# QCLogic_Rev_A_Sht5_MEMS.net
KiCad netlist of a schematic drawn in Altium Designer
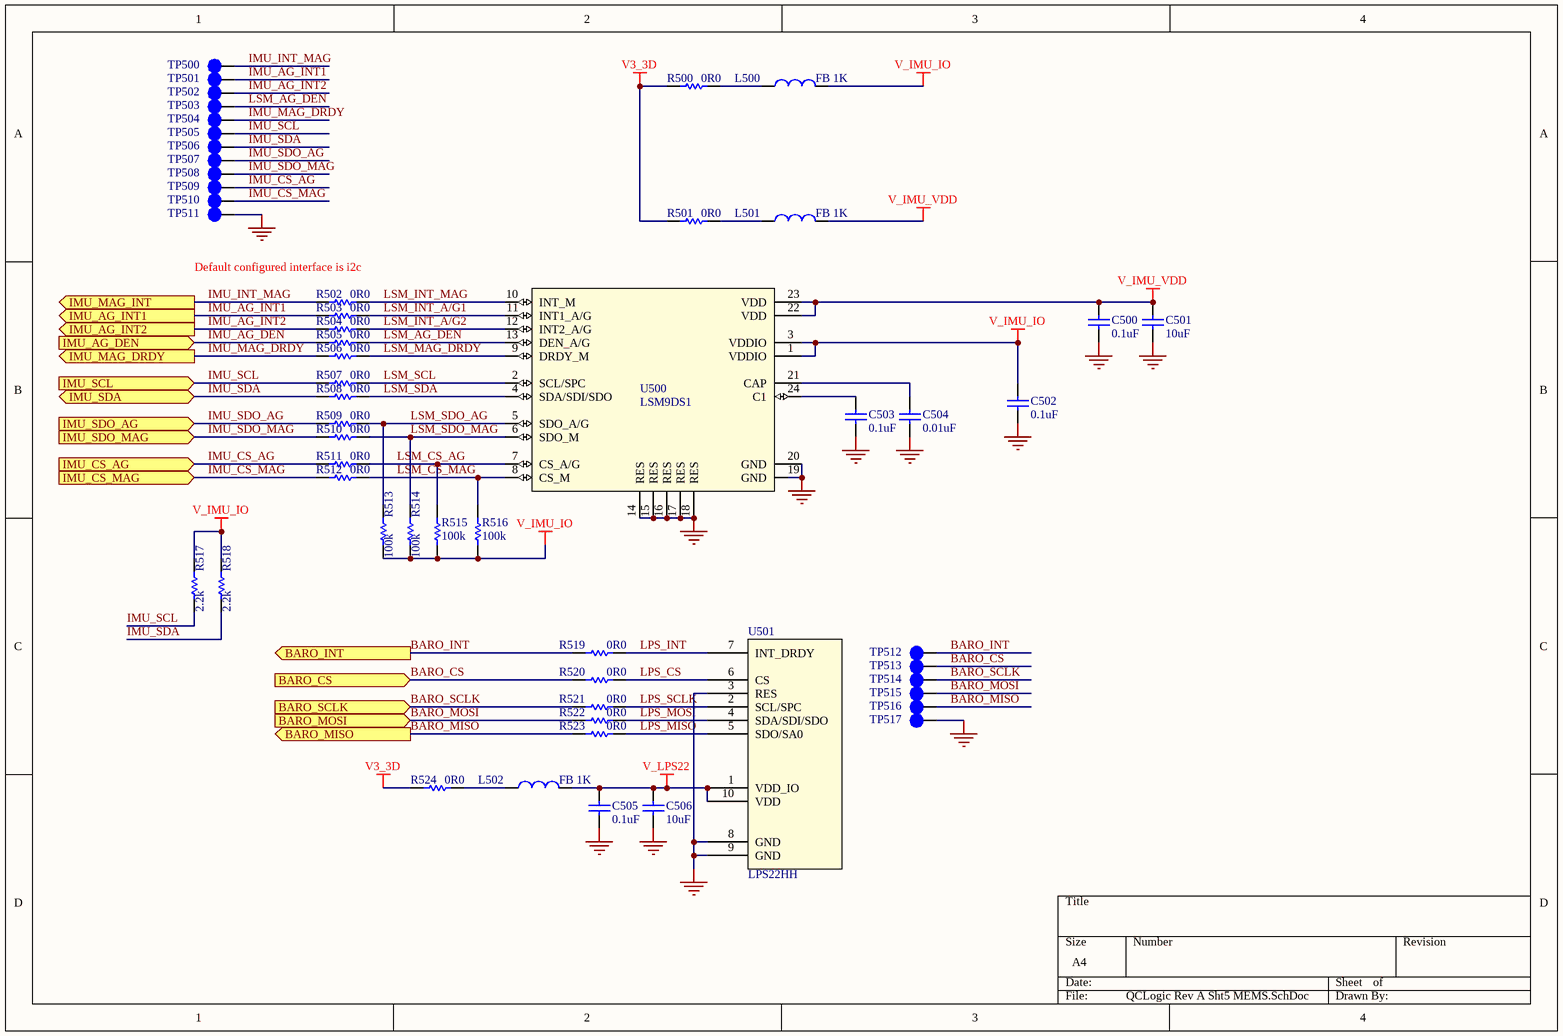
[diagram p0: QCLogic Rev A Sht5 MEMS.SchDoc]

(export (version "E")
  (design (tool "Eeschema 10.0.6"))
  (components
    (comp (ref "C500")
      (value "0.1uF")
      (footprint "SMD CAP 0402")
      (description "CAP CER 0.1UF 25V X7R 0402")
      (fields (field (name "2. MANUFACTURER PART NUMBER") "CC0402KRX7R8BB104"))
      (libsource (lib "SBCLib") (part "CAP MLCC SMD"))
    )
    (comp (ref "C501")
      (value "10uF")
      (footprint "SMD CAP 0805")
      (description "CAP CER 10UF 25V X5R 0805")
      (fields (field (name "2. MANUFACTURER PART NUMBER") "TMK212BBJ106KG-T"))
      (libsource (lib "SBCLib") (part "CAP MLCC SMD"))
    )
    (comp (ref "C502")
      (value "0.1uF")
      (footprint "SMD CAP 0402")
      (description "CAP CER 0.1UF 25V X7R 0402")
      (fields (field (name "2. MANUFACTURER PART NUMBER") "CC0402KRX7R8BB104"))
      (libsource (lib "SBCLib") (part "CAP MLCC SMD"))
    )
    (comp (ref "C503")
      (value "0.1uF")
      (footprint "SMD CAP 0402")
      (description "CAP CER 0.1UF 25V X7R 0402")
      (fields (field (name "2. MANUFACTURER PART NUMBER") "CC0402KRX7R8BB104"))
      (libsource (lib "SBCLib") (part "CAP MLCC SMD"))
    )
    (comp (ref "C504")
      (value "0.01uF")
      (footprint "SMD CAP 0402")
      (description "CAP CER 10000PF 16V X7R 0402")
      (fields (field (name "2. MANUFACTURER PART NUMBER") "0402B103K160CT"))
      (libsource (lib "SBCLib") (part "CAP MLCC SMD"))
    )
    (comp (ref "C505")
      (value "0.1uF")
      (footprint "SMD CAP 0402")
      (description "CAP CER 0.1UF 25V X7R 0402")
      (fields (field (name "2. MANUFACTURER PART NUMBER") "CC0402KRX7R8BB104"))
      (libsource (lib "SBCLib") (part "CAP MLCC SMD"))
    )
    (comp (ref "C506")
      (value "10uF")
      (footprint "SMD CAP 0805")
      (description "CAP CER 10UF 25V X5R 0805")
      (fields (field (name "2. MANUFACTURER PART NUMBER") "TMK212BBJ106KG-T"))
      (libsource (lib "SBCLib") (part "CAP MLCC SMD"))
    )
    (comp (ref "L500")
      (value "FB 1K")
      (footprint "SMD RES 0402")
      (description "FERRITE BEAD 1 KOHM 0402 1LN")
      (fields (field (name "2. MANUFACTURER PART NUMBER") "BLM15HD102SN1D"))
      (libsource (lib "SBCLib") (part "INDUCTOR"))
    )
    (comp (ref "L501")
      (value "FB 1K")
      (footprint "SMD RES 0402")
      (description "FERRITE BEAD 1 KOHM 0402 1LN")
      (fields (field (name "2. MANUFACTURER PART NUMBER") "BLM15HD102SN1D"))
      (libsource (lib "SBCLib") (part "INDUCTOR"))
    )
    (comp (ref "L502")
      (value "FB 1K")
      (footprint "SMD RES 0402")
      (description "FERRITE BEAD 1 KOHM 0402 1LN")
      (fields (field (name "2. MANUFACTURER PART NUMBER") "BLM15HD102SN1D"))
      (libsource (lib "SBCLib") (part "INDUCTOR"))
    )
    (comp (ref "R500")
      (value "0R0")
      (footprint "SMD RES 0402")
      (description "RES SMD 0 OHM JUMPER 1/16W 0402")
      (fields (field (name "2. MANUFACTURER PART NUMBER") "RC0402FR-070RL"))
      (libsource (lib "SBCLib") (part "RES SMD"))
    )
    (comp (ref "R501")
      (value "0R0")
      (footprint "SMD RES 0402")
      (description "RES SMD 0 OHM JUMPER 1/16W 0402")
      (fields (field (name "2. MANUFACTURER PART NUMBER") "RC0402FR-070RL"))
      (libsource (lib "SBCLib") (part "RES SMD"))
    )
    (comp (ref "R502")
      (value "0R0")
      (footprint "SMD RES 0402")
      (description "RES SMD 0 OHM JUMPER 1/16W 0402")
      (fields (field (name "2. MANUFACTURER PART NUMBER") "RC0402FR-070RL"))
      (libsource (lib "SBCLib") (part "RES SMD"))
    )
    (comp (ref "R503")
      (value "0R0")
      (footprint "SMD RES 0402")
      (description "RES SMD 0 OHM JUMPER 1/16W 0402")
      (fields (field (name "2. MANUFACTURER PART NUMBER") "RC0402FR-070RL"))
      (libsource (lib "SBCLib") (part "RES SMD"))
    )
    (comp (ref "R504")
      (value "0R0")
      (footprint "SMD RES 0402")
      (description "RES SMD 0 OHM JUMPER 1/16W 0402")
      (fields (field (name "2. MANUFACTURER PART NUMBER") "RC0402FR-070RL"))
      (libsource (lib "SBCLib") (part "RES SMD"))
    )
    (comp (ref "R505")
      (value "0R0")
      (footprint "SMD RES 0402")
      (description "RES SMD 0 OHM JUMPER 1/16W 0402")
      (fields (field (name "2. MANUFACTURER PART NUMBER") "RC0402FR-070RL"))
      (libsource (lib "SBCLib") (part "RES SMD"))
    )
    (comp (ref "R506")
      (value "0R0")
      (footprint "SMD RES 0402")
      (description "RES SMD 0 OHM JUMPER 1/16W 0402")
      (fields (field (name "2. MANUFACTURER PART NUMBER") "RC0402FR-070RL"))
      (libsource (lib "SBCLib") (part "RES SMD"))
    )
    (comp (ref "R507")
      (value "0R0")
      (footprint "SMD RES 0402")
      (description "RES SMD 0 OHM JUMPER 1/16W 0402")
      (fields (field (name "2. MANUFACTURER PART NUMBER") "RC0402FR-070RL"))
      (libsource (lib "SBCLib") (part "RES SMD"))
    )
    (comp (ref "R508")
      (value "0R0")
      (footprint "SMD RES 0402")
      (description "RES SMD 0 OHM JUMPER 1/16W 0402")
      (fields (field (name "2. MANUFACTURER PART NUMBER") "RC0402FR-070RL"))
      (libsource (lib "SBCLib") (part "RES SMD"))
    )
    (comp (ref "R509")
      (value "0R0")
      (footprint "SMD RES 0402")
      (description "RES SMD 0 OHM JUMPER 1/16W 0402")
      (fields (field (name "2. MANUFACTURER PART NUMBER") "RC0402FR-070RL"))
      (libsource (lib "SBCLib") (part "RES SMD"))
    )
    (comp (ref "R510")
      (value "0R0")
      (footprint "SMD RES 0402")
      (description "RES SMD 0 OHM JUMPER 1/16W 0402")
      (fields (field (name "2. MANUFACTURER PART NUMBER") "RC0402FR-070RL"))
      (libsource (lib "SBCLib") (part "RES SMD"))
    )
    (comp (ref "R511")
      (value "0R0")
      (footprint "SMD RES 0402")
      (description "RES SMD 0 OHM JUMPER 1/16W 0402")
      (fields (field (name "2. MANUFACTURER PART NUMBER") "RC0402FR-070RL"))
      (libsource (lib "SBCLib") (part "RES SMD"))
    )
    (comp (ref "R512")
      (value "0R0")
      (footprint "SMD RES 0402")
      (description "RES SMD 0 OHM JUMPER 1/16W 0402")
      (fields (field (name "2. MANUFACTURER PART NUMBER") "RC0402FR-070RL"))
      (libsource (lib "SBCLib") (part "RES SMD"))
    )
    (comp (ref "R513")
      (value "100k")
      (footprint "SMD RES 0402")
      (description "RES SMD 100K OHM 1% 1/16W 0402")
      (fields (field (name "2. MANUFACTURER PART NUMBER") "RC0402FR-07100KL"))
      (libsource (lib "SBCLib") (part "RES SMD"))
    )
    (comp (ref "R514")
      (value "100k")
      (footprint "SMD RES 0402")
      (description "RES SMD 100K OHM 1% 1/16W 0402")
      (fields (field (name "2. MANUFACTURER PART NUMBER") "RC0402FR-07100KL"))
      (libsource (lib "SBCLib") (part "RES SMD"))
    )
    (comp (ref "R515")
      (value "100k")
      (footprint "SMD RES 0402")
      (description "RES SMD 100K OHM 1% 1/16W 0402")
      (fields (field (name "2. MANUFACTURER PART NUMBER") "RC0402FR-07100KL"))
      (libsource (lib "SBCLib") (part "RES SMD"))
    )
    (comp (ref "R516")
      (value "100k")
      (footprint "SMD RES 0402")
      (description "RES SMD 100K OHM 1% 1/16W 0402")
      (fields (field (name "2. MANUFACTURER PART NUMBER") "RC0402FR-07100KL"))
      (libsource (lib "SBCLib") (part "RES SMD"))
    )
    (comp (ref "R517")
      (value "2.2k")
      (footprint "SMD RES 0402")
      (description "RES SMD 2.2K OHM 1% 1/16W 0402")
      (fields (field (name "2. MANUFACTURER PART NUMBER") "RC0402FR-072K2L"))
      (libsource (lib "SBCLib") (part "RES SMD"))
    )
    (comp (ref "R518")
      (value "2.2k")
      (footprint "SMD RES 0402")
      (description "RES SMD 2.2K OHM 1% 1/16W 0402")
      (fields (field (name "2. MANUFACTURER PART NUMBER") "RC0402FR-072K2L"))
      (libsource (lib "SBCLib") (part "RES SMD"))
    )
    (comp (ref "R519")
      (value "0R0")
      (footprint "SMD RES 0402")
      (description "RES SMD 0 OHM JUMPER 1/16W 0402")
      (fields (field (name "2. MANUFACTURER PART NUMBER") "RC0402FR-070RL"))
      (libsource (lib "SBCLib") (part "RES SMD"))
    )
    (comp (ref "R520")
      (value "0R0")
      (footprint "SMD RES 0402")
      (description "RES SMD 0 OHM JUMPER 1/16W 0402")
      (fields (field (name "2. MANUFACTURER PART NUMBER") "RC0402FR-070RL"))
      (libsource (lib "SBCLib") (part "RES SMD"))
    )
    (comp (ref "R521")
      (value "0R0")
      (footprint "SMD RES 0402")
      (description "RES SMD 0 OHM JUMPER 1/16W 0402")
      (fields (field (name "2. MANUFACTURER PART NUMBER") "RC0402FR-070RL"))
      (libsource (lib "SBCLib") (part "RES SMD"))
    )
    (comp (ref "R522")
      (value "0R0")
      (footprint "SMD RES 0402")
      (description "RES SMD 0 OHM JUMPER 1/16W 0402")
      (fields (field (name "2. MANUFACTURER PART NUMBER") "RC0402FR-070RL"))
      (libsource (lib "SBCLib") (part "RES SMD"))
    )
    (comp (ref "R523")
      (value "0R0")
      (footprint "SMD RES 0402")
      (description "RES SMD 0 OHM JUMPER 1/16W 0402")
      (fields (field (name "2. MANUFACTURER PART NUMBER") "RC0402FR-070RL"))
      (libsource (lib "SBCLib") (part "RES SMD"))
    )
    (comp (ref "R524")
      (value "0R0")
      (footprint "SMD RES 0402")
      (description "RES SMD 0 OHM JUMPER 1/16W 0402")
      (fields (field (name "2. MANUFACTURER PART NUMBER") "RC0402FR-070RL"))
      (libsource (lib "SBCLib") (part "RES SMD"))
    )
    (comp (ref "TP500")
      (value "TESTPOINT SMD")
      (footprint "TESTPOINT 0.5mm DIA")
      (description "TESTPOINT SMD PAD")
      (libsource (lib "SBCLib") (part "TESTPOINT PAD"))
    )
    (comp (ref "TP501")
      (value "TESTPOINT SMD")
      (footprint "TESTPOINT 0.5mm DIA")
      (description "TESTPOINT SMD PAD")
      (libsource (lib "SBCLib") (part "TESTPOINT PAD"))
    )
    (comp (ref "TP502")
      (value "TESTPOINT SMD")
      (footprint "TESTPOINT 0.5mm DIA")
      (description "TESTPOINT SMD PAD")
      (libsource (lib "SBCLib") (part "TESTPOINT PAD"))
    )
    (comp (ref "TP503")
      (value "TESTPOINT SMD")
      (footprint "TESTPOINT 0.5mm DIA")
      (description "TESTPOINT SMD PAD")
      (libsource (lib "SBCLib") (part "TESTPOINT PAD"))
    )
    (comp (ref "TP504")
      (value "TESTPOINT SMD")
      (footprint "TESTPOINT 0.5mm DIA")
      (description "TESTPOINT SMD PAD")
      (libsource (lib "SBCLib") (part "TESTPOINT PAD"))
    )
    (comp (ref "TP505")
      (value "TESTPOINT SMD")
      (footprint "TESTPOINT 0.5mm DIA")
      (description "TESTPOINT SMD PAD")
      (libsource (lib "SBCLib") (part "TESTPOINT PAD"))
    )
    (comp (ref "TP506")
      (value "TESTPOINT SMD")
      (footprint "TESTPOINT 0.5mm DIA")
      (description "TESTPOINT SMD PAD")
      (libsource (lib "SBCLib") (part "TESTPOINT PAD"))
    )
    (comp (ref "TP507")
      (value "TESTPOINT SMD")
      (footprint "TESTPOINT 0.5mm DIA")
      (description "TESTPOINT SMD PAD")
      (libsource (lib "SBCLib") (part "TESTPOINT PAD"))
    )
    (comp (ref "TP508")
      (value "TESTPOINT SMD")
      (footprint "TESTPOINT 0.5mm DIA")
      (description "TESTPOINT SMD PAD")
      (libsource (lib "SBCLib") (part "TESTPOINT PAD"))
    )
    (comp (ref "TP509")
      (value "TESTPOINT SMD")
      (footprint "TESTPOINT 0.5mm DIA")
      (description "TESTPOINT SMD PAD")
      (libsource (lib "SBCLib") (part "TESTPOINT PAD"))
    )
    (comp (ref "TP510")
      (value "TESTPOINT SMD")
      (footprint "TESTPOINT 0.5mm DIA")
      (description "TESTPOINT SMD PAD")
      (libsource (lib "SBCLib") (part "TESTPOINT PAD"))
    )
    (comp (ref "TP511")
      (value "TESTPOINT SMD")
      (footprint "TESTPOINT 1mm DIA")
      (description "TESTPOINT SMD PAD")
      (libsource (lib "SBCLib") (part "TESTPOINT PAD"))
    )
    (comp (ref "TP512")
      (value "TESTPOINT SMD")
      (footprint "TESTPOINT 0.5mm DIA")
      (description "TESTPOINT SMD PAD")
      (libsource (lib "SBCLib") (part "TESTPOINT PAD"))
    )
    (comp (ref "TP513")
      (value "TESTPOINT SMD")
      (footprint "TESTPOINT 0.5mm DIA")
      (description "TESTPOINT SMD PAD")
      (libsource (lib "SBCLib") (part "TESTPOINT PAD"))
    )
    (comp (ref "TP514")
      (value "TESTPOINT SMD")
      (footprint "TESTPOINT 0.5mm DIA")
      (description "TESTPOINT SMD PAD")
      (libsource (lib "SBCLib") (part "TESTPOINT PAD"))
    )
    (comp (ref "TP515")
      (value "TESTPOINT SMD")
      (footprint "TESTPOINT 0.5mm DIA")
      (description "TESTPOINT SMD PAD")
      (libsource (lib "SBCLib") (part "TESTPOINT PAD"))
    )
    (comp (ref "TP516")
      (value "TESTPOINT SMD")
      (footprint "TESTPOINT 0.5mm DIA")
      (description "TESTPOINT SMD PAD")
      (libsource (lib "SBCLib") (part "TESTPOINT PAD"))
    )
    (comp (ref "TP517")
      (value "TESTPOINT SMD")
      (footprint "TESTPOINT 0.5mm DIA")
      (description "TESTPOINT SMD PAD")
      (libsource (lib "SBCLib") (part "TESTPOINT PAD"))
    )
    (comp (ref "U500")
      (value "LSM9DS1")
      (footprint "LGA-24")
      (description "IMU ACCEL/GYRO/MAG I2C/SPI 24LGA LSM9DS1")
      (fields (field (name "2. MANUFACTURER PART NUMBER") "LSM9DS1TR"))
      (libsource (lib "SBCLib") (part "IC IMU ACCEL/GYRO/MAG I2C/SPI 24LGA LSM9DS1"))
    )
    (comp (ref "U501")
      (value "LPS22HH")
      (footprint "LGA-10")
      (description "IC BARO PRESSURE SENSOR LPS22HH")
      (fields (field (name "2. MANUFACTURER PART NUMBER") "LPS22HHTR"))
      (libsource (lib "SBCLib") (part "IC BARO PRESSURE SENSOR LPS22HH"))
    )
  )
  (nets
    (net (code "1") (name "/BARO_CS") (class "Default")
      (node (ref "R520") (pin "1") (pinfunction "1_1") (pintype "passive"))
      (node (ref "TP513") (pin "1") (pinfunction "1_1") (pintype "passive"))
    )
    (net (code "2") (name "/BARO_INT") (class "Default")
      (node (ref "R519") (pin "1") (pinfunction "1_1") (pintype "passive"))
      (node (ref "TP512") (pin "1") (pinfunction "1_1") (pintype "passive"))
    )
    (net (code "3") (name "/BARO_MISO") (class "Default")
      (node (ref "R523") (pin "1") (pinfunction "1_1") (pintype "passive"))
      (node (ref "TP516") (pin "1") (pinfunction "1_1") (pintype "passive"))
    )
    (net (code "4") (name "/BARO_MOSI") (class "Default")
      (node (ref "R522") (pin "1") (pinfunction "1_1") (pintype "passive"))
      (node (ref "TP515") (pin "1") (pinfunction "1_1") (pintype "passive"))
    )
    (net (code "5") (name "/BARO_SCLK") (class "Default")
      (node (ref "R521") (pin "1") (pinfunction "1_1") (pintype "passive"))
      (node (ref "TP514") (pin "1") (pinfunction "1_1") (pintype "passive"))
    )
    (net (code "6") (name "/IMU_AG_DEN") (class "Default")
      (node (ref "R505") (pin "1") (pinfunction "1_1") (pintype "passive"))
    )
    (net (code "7") (name "/IMU_AG_INT1") (class "Default")
      (node (ref "R503") (pin "1") (pinfunction "1_1") (pintype "passive"))
      (node (ref "TP501") (pin "1") (pinfunction "1_1") (pintype "passive"))
    )
    (net (code "8") (name "/IMU_AG_INT2") (class "Default")
      (node (ref "R504") (pin "1") (pinfunction "1_1") (pintype "passive"))
      (node (ref "TP502") (pin "1") (pinfunction "1_1") (pintype "passive"))
    )
    (net (code "9") (name "/IMU_CS_AG") (class "Default")
      (node (ref "R511") (pin "1") (pinfunction "1_1") (pintype "passive"))
      (node (ref "TP509") (pin "1") (pinfunction "1_1") (pintype "passive"))
    )
    (net (code "10") (name "/IMU_CS_MAG") (class "Default")
      (node (ref "R512") (pin "1") (pinfunction "1_1") (pintype "passive"))
      (node (ref "TP510") (pin "1") (pinfunction "1_1") (pintype "passive"))
    )
    (net (code "11") (name "/IMU_INT_MAG") (class "Default")
      (node (ref "R502") (pin "1") (pinfunction "1_1") (pintype "passive"))
      (node (ref "TP500") (pin "1") (pinfunction "1_1") (pintype "passive"))
    )
    (net (code "12") (name "/IMU_MAG_DRDY") (class "Default")
      (node (ref "R506") (pin "1") (pinfunction "1_1") (pintype "passive"))
      (node (ref "TP504") (pin "1") (pinfunction "1_1") (pintype "passive"))
    )
    (net (code "13") (name "/IMU_SCL") (class "Default")
      (node (ref "R507") (pin "1") (pinfunction "1_1") (pintype "passive"))
      (node (ref "R517") (pin "2") (pinfunction "2_2") (pintype "passive"))
      (node (ref "TP505") (pin "1") (pinfunction "1_1") (pintype "passive"))
    )
    (net (code "14") (name "/IMU_SDA") (class "Default")
      (node (ref "R508") (pin "1") (pinfunction "1_1") (pintype "passive"))
      (node (ref "R518") (pin "2") (pinfunction "2_2") (pintype "passive"))
      (node (ref "TP506") (pin "1") (pinfunction "1_1") (pintype "passive"))
    )
    (net (code "15") (name "/IMU_SDO_AG") (class "Default")
      (node (ref "R509") (pin "1") (pinfunction "1_1") (pintype "passive"))
      (node (ref "TP507") (pin "1") (pinfunction "1_1") (pintype "passive"))
    )
    (net (code "16") (name "/IMU_SDO_MAG") (class "Default")
      (node (ref "R510") (pin "1") (pinfunction "1_1") (pintype "passive"))
      (node (ref "TP508") (pin "1") (pinfunction "1_1") (pintype "passive"))
    )
    (net (code "17") (name "/LPS_CS") (class "Default")
      (node (ref "R520") (pin "2") (pinfunction "2_2") (pintype "passive"))
      (node (ref "U501") (pin "6") (pinfunction "CS_6") (pintype "passive"))
    )
    (net (code "18") (name "/LPS_INT") (class "Default")
      (node (ref "R519") (pin "2") (pinfunction "2_2") (pintype "passive"))
      (node (ref "U501") (pin "7") (pinfunction "INT_DRDY_7") (pintype "passive"))
    )
    (net (code "19") (name "/LPS_MISO") (class "Default")
      (node (ref "R523") (pin "2") (pinfunction "2_2") (pintype "passive"))
      (node (ref "U501") (pin "5") (pinfunction "SDO/SA0_5") (pintype "passive"))
    )
    (net (code "20") (name "/LPS_MOSI") (class "Default")
      (node (ref "R522") (pin "2") (pinfunction "2_2") (pintype "passive"))
      (node (ref "U501") (pin "4") (pinfunction "SDA/SDI/SDO_4") (pintype "passive"))
    )
    (net (code "21") (name "/LPS_SCLK") (class "Default")
      (node (ref "R521") (pin "2") (pinfunction "2_2") (pintype "passive"))
      (node (ref "U501") (pin "2") (pinfunction "SCL/SPC_2") (pintype "passive"))
    )
    (net (code "22") (name "/LSM_AG_DEN") (class "Default")
      (node (ref "R505") (pin "2") (pinfunction "2_2") (pintype "passive"))
      (node (ref "TP503") (pin "1") (pinfunction "1_1") (pintype "passive"))
      (node (ref "U500") (pin "13") (pinfunction "DEN_A/G_13") (pintype "bidirectional"))
    )
    (net (code "23") (name "/LSM_CS_AG") (class "Default")
      (node (ref "R511") (pin "2") (pinfunction "2_2") (pintype "passive"))
      (node (ref "R515") (pin "1") (pinfunction "1_1") (pintype "passive"))
      (node (ref "U500") (pin "7") (pinfunction "CS_A/G_7") (pintype "bidirectional"))
    )
    (net (code "24") (name "/LSM_CS_MAG") (class "Default")
      (node (ref "R512") (pin "2") (pinfunction "2_2") (pintype "passive"))
      (node (ref "R516") (pin "1") (pinfunction "1_1") (pintype "passive"))
      (node (ref "U500") (pin "8") (pinfunction "CS_M_8") (pintype "bidirectional"))
    )
    (net (code "25") (name "/LSM_INT_A{slash}G1") (class "Default")
      (node (ref "R503") (pin "2") (pinfunction "2_2") (pintype "passive"))
      (node (ref "U500") (pin "11") (pinfunction "INT1_A/G_11") (pintype "bidirectional"))
    )
    (net (code "26") (name "/LSM_INT_A{slash}G2") (class "Default")
      (node (ref "R504") (pin "2") (pinfunction "2_2") (pintype "passive"))
      (node (ref "U500") (pin "12") (pinfunction "INT2_A/G_12") (pintype "bidirectional"))
    )
    (net (code "27") (name "/LSM_INT_MAG") (class "Default")
      (node (ref "R502") (pin "2") (pinfunction "2_2") (pintype "passive"))
      (node (ref "U500") (pin "10") (pinfunction "INT_M_10") (pintype "bidirectional"))
    )
    (net (code "28") (name "/LSM_MAG_DRDY") (class "Default")
      (node (ref "R506") (pin "2") (pinfunction "2_2") (pintype "passive"))
      (node (ref "U500") (pin "9") (pinfunction "DRDY_M_9") (pintype "bidirectional"))
    )
    (net (code "29") (name "/LSM_SCL") (class "Default")
      (node (ref "R507") (pin "2") (pinfunction "2_2") (pintype "passive"))
      (node (ref "U500") (pin "2") (pinfunction "SCL/SPC_2") (pintype "bidirectional"))
    )
    (net (code "30") (name "/LSM_SDA") (class "Default")
      (node (ref "R508") (pin "2") (pinfunction "2_2") (pintype "passive"))
      (node (ref "U500") (pin "4") (pinfunction "SDA/SDI/SDO_4") (pintype "bidirectional"))
    )
    (net (code "31") (name "/LSM_SDO_AG") (class "Default")
      (node (ref "R509") (pin "2") (pinfunction "2_2") (pintype "passive"))
      (node (ref "R513") (pin "1") (pinfunction "1_1") (pintype "passive"))
      (node (ref "U500") (pin "5") (pinfunction "SDO_A/G_5") (pintype "bidirectional"))
    )
    (net (code "32") (name "/LSM_SDO_MAG") (class "Default")
      (node (ref "R510") (pin "2") (pinfunction "2_2") (pintype "passive"))
      (node (ref "R514") (pin "1") (pinfunction "1_1") (pintype "passive"))
      (node (ref "U500") (pin "6") (pinfunction "SDO_M_6") (pintype "bidirectional"))
    )
    (net (code "33") (name "GND") (class "Default")
      (node (ref "C500") (pin "1") (pinfunction "1_1") (pintype "passive"))
      (node (ref "C501") (pin "2") (pinfunction "2_2") (pintype "passive"))
      (node (ref "C502") (pin "1") (pinfunction "1_1") (pintype "passive"))
      (node (ref "C503") (pin "1") (pinfunction "1_1") (pintype "passive"))
      (node (ref "C504") (pin "2") (pinfunction "2_2") (pintype "passive"))
      (node (ref "C505") (pin "1") (pinfunction "1_1") (pintype "passive"))
      (node (ref "C506") (pin "2") (pinfunction "2_2") (pintype "passive"))
      (node (ref "TP511") (pin "1") (pinfunction "1_1") (pintype "passive"))
      (node (ref "TP517") (pin "1") (pinfunction "1_1") (pintype "passive"))
      (node (ref "U500") (pin "14") (pinfunction "RES_14") (pintype "passive"))
      (node (ref "U500") (pin "15") (pinfunction "RES_15") (pintype "passive"))
      (node (ref "U500") (pin "16") (pinfunction "RES_16") (pintype "passive"))
      (node (ref "U500") (pin "17") (pinfunction "RES_17") (pintype "passive"))
      (node (ref "U500") (pin "18") (pinfunction "RES_18") (pintype "passive"))
      (node (ref "U500") (pin "19") (pinfunction "GND_19") (pintype "power_in"))
      (node (ref "U500") (pin "20") (pinfunction "GND_20") (pintype "power_in"))
      (node (ref "U501") (pin "3") (pinfunction "RES_3") (pintype "passive"))
      (node (ref "U501") (pin "8") (pinfunction "GND_8") (pintype "passive"))
      (node (ref "U501") (pin "9") (pinfunction "GND_9") (pintype "passive"))
    )
    (net (code "34") (name "Net-(L500-Pad1)") (class "Default")
      (node (ref "L500") (pin "1") (pinfunction "1_1") (pintype "passive"))
      (node (ref "R500") (pin "2") (pinfunction "2_2") (pintype "passive"))
    )
    (net (code "35") (name "Net-(L501-Pad1)") (class "Default")
      (node (ref "L501") (pin "1") (pinfunction "1_1") (pintype "passive"))
      (node (ref "R501") (pin "2") (pinfunction "2_2") (pintype "passive"))
    )
    (net (code "36") (name "Net-(L502-Pad1)") (class "Default")
      (node (ref "L502") (pin "1") (pinfunction "1_1") (pintype "passive"))
      (node (ref "R524") (pin "2") (pinfunction "2_2") (pintype "passive"))
    )
    (net (code "37") (name "Net-(U500-C1)") (class "Default")
      (node (ref "C503") (pin "2") (pinfunction "2_2") (pintype "passive"))
      (node (ref "U500") (pin "24") (pinfunction "C1_24") (pintype "bidirectional"))
    )
    (net (code "38") (name "Net-(U500-CAP)") (class "Default")
      (node (ref "C504") (pin "1") (pinfunction "1_1") (pintype "passive"))
      (node (ref "U500") (pin "21") (pinfunction "CAP_21") (pintype "passive"))
    )
    (net (code "39") (name "V3_3D") (class "Default")
      (node (ref "R500") (pin "1") (pinfunction "1_1") (pintype "passive"))
      (node (ref "R501") (pin "1") (pinfunction "1_1") (pintype "passive"))
      (node (ref "R524") (pin "1") (pinfunction "1_1") (pintype "passive"))
    )
    (net (code "40") (name "V_IMU_IO") (class "Default")
      (node (ref "C502") (pin "2") (pinfunction "2_2") (pintype "passive"))
      (node (ref "L500") (pin "2") (pinfunction "2_2") (pintype "passive"))
      (node (ref "R513") (pin "2") (pinfunction "2_2") (pintype "passive"))
      (node (ref "R514") (pin "2") (pinfunction "2_2") (pintype "passive"))
      (node (ref "R515") (pin "2") (pinfunction "2_2") (pintype "passive"))
      (node (ref "R516") (pin "2") (pinfunction "2_2") (pintype "passive"))
      (node (ref "R517") (pin "1") (pinfunction "1_1") (pintype "passive"))
      (node (ref "R518") (pin "1") (pinfunction "1_1") (pintype "passive"))
      (node (ref "U500") (pin "1") (pinfunction "VDDIO_1") (pintype "power_in"))
      (node (ref "U500") (pin "3") (pinfunction "VDDIO_3") (pintype "power_in"))
    )
    (net (code "41") (name "V_IMU_VDD") (class "Default")
      (node (ref "C500") (pin "2") (pinfunction "2_2") (pintype "passive"))
      (node (ref "C501") (pin "1") (pinfunction "1_1") (pintype "passive"))
      (node (ref "L501") (pin "2") (pinfunction "2_2") (pintype "passive"))
      (node (ref "U500") (pin "22") (pinfunction "VDD_22") (pintype "power_in"))
      (node (ref "U500") (pin "23") (pinfunction "VDD_23") (pintype "power_in"))
    )
    (net (code "42") (name "V_LPS22") (class "Default")
      (node (ref "C505") (pin "2") (pinfunction "2_2") (pintype "passive"))
      (node (ref "C506") (pin "1") (pinfunction "1_1") (pintype "passive"))
      (node (ref "L502") (pin "2") (pinfunction "2_2") (pintype "passive"))
      (node (ref "U501") (pin "1") (pinfunction "VDD_IO_1") (pintype "power_in"))
      (node (ref "U501") (pin "10") (pinfunction "VDD_10") (pintype "power_in"))
    )
  )
)
